# CAN_Injector_rev1.net
KiCad netlist of a schematic drawn in EAGLE
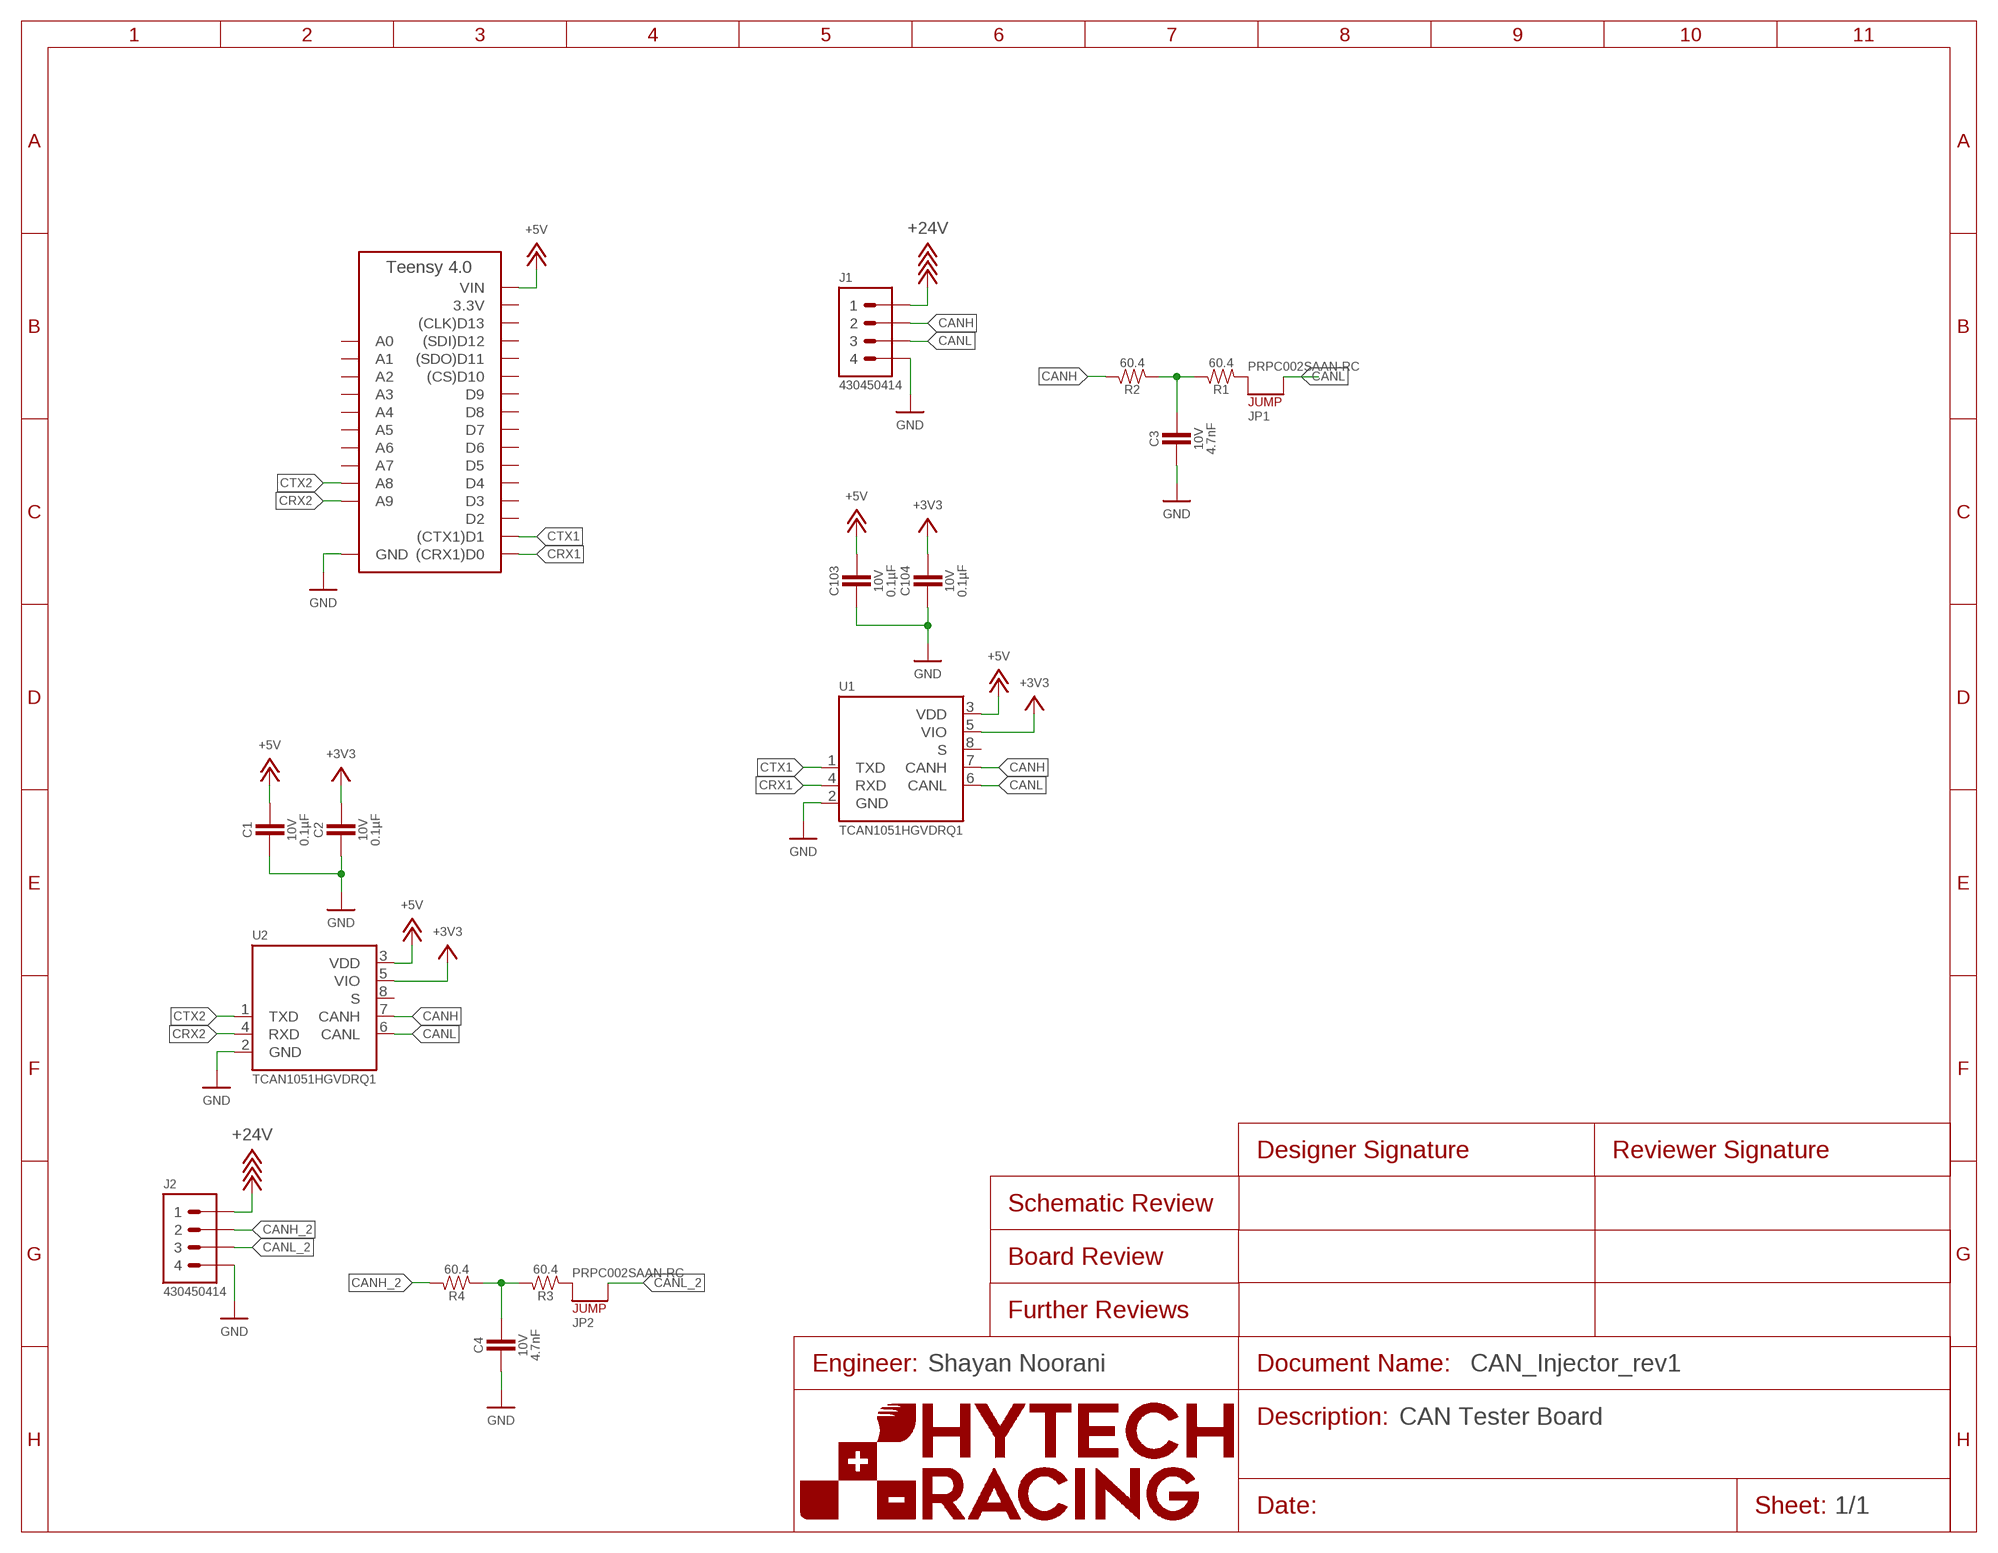
[diagram p0: schematic, sheet 1]

(export (version "E")
  (design (tool "Eeschema 10.0.6"))
  (components
    (comp (ref "A1")
      (value "TEENSY_4.0")
      (footprint "eagle-import:TEENSY_SHORT")
      (libsource (lib "eagle-import") (part "TEENSY_4.0"))
    )
    (comp (ref "C1")
      (value "CAPACITOR_0603_10V_0.1UF")
      (footprint "eagle-import:0603-CAP")
      (fields
        (field (name "CAPACITANCE") "0.1µF")
        (field (name "MANUFACTURER") "Vishay Vitramon")
        (field (name "MPN") "VJ0603Y104JXQPW1BC")
        (field (name "TOLERANCE") "5%")
        (field (name "VOLTAGE") "10V")
      )
      (libsource (lib "eagle-import") (part "CAPACITOR_?_060310V_0.1UF"))
    )
    (comp (ref "C2")
      (value "CAPACITOR_0603_10V_0.1UF")
      (footprint "eagle-import:0603-CAP")
      (fields
        (field (name "CAPACITANCE") "0.1µF")
        (field (name "MANUFACTURER") "Vishay Vitramon")
        (field (name "MPN") "VJ0603Y104JXQPW1BC")
        (field (name "TOLERANCE") "5%")
        (field (name "VOLTAGE") "10V")
      )
      (libsource (lib "eagle-import") (part "CAPACITOR_?_060310V_0.1UF"))
    )
    (comp (ref "C3")
      (value "CAPACITOR_0603_10V_4.7NF")
      (footprint "eagle-import:0603-CAP")
      (fields
        (field (name "CAPACITANCE") "4.7nF")
        (field (name "MANUFACTURER") "Würth Elektronik")
        (field (name "MPN") "885012206012")
        (field (name "TOLERANCE") "10%")
        (field (name "VOLTAGE") "10V")
      )
      (libsource (lib "eagle-import") (part "CAPACITOR_?_060310V_4.7NF"))
    )
    (comp (ref "C4")
      (value "CAPACITOR_0603_10V_4.7NF")
      (footprint "eagle-import:0603-CAP")
      (fields
        (field (name "CAPACITANCE") "4.7nF")
        (field (name "MANUFACTURER") "Würth Elektronik")
        (field (name "MPN") "885012206012")
        (field (name "TOLERANCE") "10%")
        (field (name "VOLTAGE") "10V")
      )
      (libsource (lib "eagle-import") (part "CAPACITOR_?_060310V_4.7NF"))
    )
    (comp (ref "C103")
      (value "CAPACITOR_0603_10V_0.1UF")
      (footprint "eagle-import:0603-CAP")
      (fields
        (field (name "CAPACITANCE") "0.1µF")
        (field (name "MANUFACTURER") "Vishay Vitramon")
        (field (name "MPN") "VJ0603Y104JXQPW1BC")
        (field (name "TOLERANCE") "5%")
        (field (name "VOLTAGE") "10V")
      )
      (libsource (lib "eagle-import") (part "CAPACITOR_?_060310V_0.1UF"))
    )
    (comp (ref "C104")
      (value "CAPACITOR_0603_10V_0.1UF")
      (footprint "eagle-import:0603-CAP")
      (fields
        (field (name "CAPACITANCE") "0.1µF")
        (field (name "MANUFACTURER") "Vishay Vitramon")
        (field (name "MPN") "VJ0603Y104JXQPW1BC")
        (field (name "TOLERANCE") "5%")
        (field (name "VOLTAGE") "10V")
      )
      (libsource (lib "eagle-import") (part "CAPACITOR_?_060310V_0.1UF"))
    )
    (comp (ref "J1")
      (value "CONNECTOR-4_μF_T_V_BLACK")
      (footprint "eagle-import:MOLEX_MICROFIT_PTH_VERTICAL_04_DUAL")
      (fields (field (name "MANUFACTURER") "Molex") (field (name "MPN") "430450414"))
      (libsource (lib "eagle-import") (part "CONNECTOR-4_?_μF_T_VBLACK"))
    )
    (comp (ref "J2")
      (value "CONNECTOR-4_μF_T_V_BLACK")
      (footprint "eagle-import:MOLEX_MICROFIT_PTH_VERTICAL_04_DUAL")
      (fields (field (name "MANUFACTURER") "Molex") (field (name "MPN") "430450414"))
      (libsource (lib "eagle-import") (part "CONNECTOR-4_?_μF_T_VBLACK"))
    )
    (comp (ref "JP1")
      (value "JUMPER__1X02")
      (footprint "eagle-import:1X02")
      (fields
        (field (name "MANUFACTURER") "Sullins Connector Solutions")
        (field (name "MPN") "PRPC002SAAN-RC")
      )
      (libsource (lib "eagle-import") (part "JUMPER_?_1X02"))
    )
    (comp (ref "JP2")
      (value "JUMPER__1X02")
      (footprint "eagle-import:1X02")
      (fields
        (field (name "MANUFACTURER") "Sullins Connector Solutions")
        (field (name "MPN") "PRPC002SAAN-RC")
      )
      (libsource (lib "eagle-import") (part "JUMPER_?_1X02"))
    )
    (comp (ref "R1")
      (value "RESISTOR_0603_60.4")
      (footprint "eagle-import:0603-RES")
      (fields
        (field (name "MANUFACTURER") "Yageo")
        (field (name "MPN") "RC0603FR-0760R4L")
        (field (name "POWER") "0.1W")
        (field (name "RESISTANCE") "60.4")
      )
      (libsource (lib "eagle-import") (part "RESISTOR_?_060360.4"))
    )
    (comp (ref "R2")
      (value "RESISTOR_0603_60.4")
      (footprint "eagle-import:0603-RES")
      (fields
        (field (name "MANUFACTURER") "Yageo")
        (field (name "MPN") "RC0603FR-0760R4L")
        (field (name "POWER") "0.1W")
        (field (name "RESISTANCE") "60.4")
      )
      (libsource (lib "eagle-import") (part "RESISTOR_?_060360.4"))
    )
    (comp (ref "R3")
      (value "RESISTOR_0603_60.4")
      (footprint "eagle-import:0603-RES")
      (fields
        (field (name "MANUFACTURER") "Yageo")
        (field (name "MPN") "RC0603FR-0760R4L")
        (field (name "POWER") "0.1W")
        (field (name "RESISTANCE") "60.4")
      )
      (libsource (lib "eagle-import") (part "RESISTOR_?_060360.4"))
    )
    (comp (ref "R4")
      (value "RESISTOR_0603_60.4")
      (footprint "eagle-import:0603-RES")
      (fields
        (field (name "MANUFACTURER") "Yageo")
        (field (name "MPN") "RC0603FR-0760R4L")
        (field (name "POWER") "0.1W")
        (field (name "RESISTANCE") "60.4")
      )
      (libsource (lib "eagle-import") (part "RESISTOR_?_060360.4"))
    )
    (comp (ref "U1")
      (value "TCAN1051HQV-Q1")
      (footprint "eagle-import:SOIC-08(NARROW,0.15_)")
      (fields (field (name "MANUFACTURER") "Texas Instruments") (field (name "MPN") "TCAN1051HGVDRQ1"))
      (libsource (lib "eagle-import") (part "TCAN1051V-Q1HQ"))
    )
    (comp (ref "U2")
      (value "TCAN1051HQV-Q1")
      (footprint "eagle-import:SOIC-08(NARROW,0.15_)")
      (fields (field (name "MANUFACTURER") "Texas Instruments") (field (name "MPN") "TCAN1051HGVDRQ1"))
      (libsource (lib "eagle-import") (part "TCAN1051V-Q1HQ"))
    )
  )
  (nets
    (net (code "1") (name "+3V3") (class "Default")
      (node (ref "C104") (pin "1") (pinfunction "1_1") (pintype "passive"))
      (node (ref "C2") (pin "1") (pinfunction "1_1") (pintype "passive"))
      (node (ref "U1") (pin "5") (pinfunction "VIO_5") (pintype "power_in"))
      (node (ref "U2") (pin "5") (pinfunction "VIO_5") (pintype "power_in"))
    )
    (net (code "2") (name "+5V") (class "Default")
      (node (ref "A1") (pin "VIN") (pinfunction "VIN_VIN") (pintype "power_in"))
      (node (ref "C1") (pin "1") (pinfunction "1_1") (pintype "passive"))
      (node (ref "C103") (pin "1") (pinfunction "1_1") (pintype "passive"))
      (node (ref "U1") (pin "3") (pinfunction "VDD_3") (pintype "power_in"))
      (node (ref "U2") (pin "3") (pinfunction "VDD_3") (pintype "power_in"))
    )
    (net (code "3") (name "+24V") (class "Default")
      (node (ref "J1") (pin "1") (pinfunction "1_1") (pintype "passive"))
      (node (ref "J2") (pin "1") (pinfunction "1_1") (pintype "passive"))
    )
    (net (code "4") (name "/3.3V") (class "Default")
      (node (ref "A1") (pin "3.3V") (pinfunction "3.3V_3.3V") (pintype "power_in"))
    )
    (net (code "5") (name "CANH") (class "Default")
      (node (ref "J1") (pin "2") (pinfunction "2_2") (pintype "passive"))
      (node (ref "R2") (pin "1") (pinfunction "1_1") (pintype "passive"))
      (node (ref "U1") (pin "7") (pinfunction "CANH_7") (pintype "output"))
      (node (ref "U2") (pin "7") (pinfunction "CANH_7") (pintype "output"))
    )
    (net (code "6") (name "CANH_2") (class "Default")
      (node (ref "J2") (pin "2") (pinfunction "2_2") (pintype "passive"))
      (node (ref "R4") (pin "1") (pinfunction "1_1") (pintype "passive"))
    )
    (net (code "7") (name "CANL") (class "Default")
      (node (ref "J1") (pin "3") (pinfunction "3_3") (pintype "passive"))
      (node (ref "JP1") (pin "2") (pinfunction "2_2") (pintype "passive"))
      (node (ref "U1") (pin "6") (pinfunction "CANL_6") (pintype "bidirectional"))
      (node (ref "U2") (pin "6") (pinfunction "CANL_6") (pintype "bidirectional"))
    )
    (net (code "8") (name "CANL_2") (class "Default")
      (node (ref "J2") (pin "3") (pinfunction "3_3") (pintype "passive"))
      (node (ref "JP2") (pin "2") (pinfunction "2_2") (pintype "passive"))
    )
    (net (code "9") (name "CRX1") (class "Default")
      (node (ref "A1") (pin "D0") (pinfunction "(CRX1)D0_D0") (pintype "bidirectional"))
      (node (ref "U1") (pin "4") (pinfunction "RXD_4") (pintype "output"))
    )
    (net (code "10") (name "CRX2") (class "Default")
      (node (ref "A1") (pin "D23") (pinfunction "A9_D23") (pintype "bidirectional"))
      (node (ref "U2") (pin "4") (pinfunction "RXD_4") (pintype "output"))
    )
    (net (code "11") (name "CTX1") (class "Default")
      (node (ref "A1") (pin "D1") (pinfunction "(CTX1)D1_D1") (pintype "bidirectional"))
      (node (ref "U1") (pin "1") (pinfunction "TXD_1") (pintype "input"))
    )
    (net (code "12") (name "CTX2") (class "Default")
      (node (ref "A1") (pin "D22") (pinfunction "A8_D22") (pintype "bidirectional"))
      (node (ref "U2") (pin "1") (pinfunction "TXD_1") (pintype "input"))
    )
    (net (code "13") (name "GND") (class "Default")
      (node (ref "A1") (pin "AGND/GND") (pinfunction "GND_AGND/GND") (pintype "power_in"))
      (node (ref "A1") (pin "GND") (pinfunction "GND_GND") (pintype "power_in"))
      (node (ref "C1") (pin "2") (pinfunction "2_2") (pintype "passive"))
      (node (ref "C103") (pin "2") (pinfunction "2_2") (pintype "passive"))
      (node (ref "C104") (pin "2") (pinfunction "2_2") (pintype "passive"))
      (node (ref "C2") (pin "2") (pinfunction "2_2") (pintype "passive"))
      (node (ref "C3") (pin "2") (pinfunction "2_2") (pintype "passive"))
      (node (ref "C4") (pin "2") (pinfunction "2_2") (pintype "passive"))
      (node (ref "J1") (pin "4") (pinfunction "4_4") (pintype "passive"))
      (node (ref "J2") (pin "4") (pinfunction "4_4") (pintype "passive"))
      (node (ref "U1") (pin "2") (pinfunction "GND_2") (pintype "power_in"))
      (node (ref "U2") (pin "2") (pinfunction "GND_2") (pintype "power_in"))
    )
    (net (code "14") (name "Net-(C3-Pad1)") (class "Default")
      (node (ref "C3") (pin "1") (pinfunction "1_1") (pintype "passive"))
      (node (ref "R1") (pin "1") (pinfunction "1_1") (pintype "passive"))
      (node (ref "R2") (pin "2") (pinfunction "2_2") (pintype "passive"))
    )
    (net (code "15") (name "Net-(C4-Pad1)") (class "Default")
      (node (ref "C4") (pin "1") (pinfunction "1_1") (pintype "passive"))
      (node (ref "R3") (pin "1") (pinfunction "1_1") (pintype "passive"))
      (node (ref "R4") (pin "2") (pinfunction "2_2") (pintype "passive"))
    )
    (net (code "16") (name "Net-(JP1-Pad1)") (class "Default")
      (node (ref "JP1") (pin "1") (pinfunction "1_1") (pintype "passive"))
      (node (ref "R1") (pin "2") (pinfunction "2_2") (pintype "passive"))
    )
    (net (code "17") (name "Net-(JP2-Pad1)") (class "Default")
      (node (ref "JP2") (pin "1") (pinfunction "1_1") (pintype "passive"))
      (node (ref "R3") (pin "2") (pinfunction "2_2") (pintype "passive"))
    )
    (net (code "18") (name "unconnected-(A1-(CLK)D13-PadD13)") (class "Default")
      (node (ref "A1") (pin "D13") (pinfunction "(CLK)D13_D13") (pintype "bidirectional"))
    )
    (net (code "19") (name "unconnected-(A1-(CS)D10-PadD10)") (class "Default")
      (node (ref "A1") (pin "D10") (pinfunction "(CS)D10_D10") (pintype "bidirectional"))
    )
    (net (code "20") (name "unconnected-(A1-(SDI)D12-PadD12)") (class "Default")
      (node (ref "A1") (pin "D12") (pinfunction "(SDI)D12_D12") (pintype "bidirectional"))
    )
    (net (code "21") (name "unconnected-(A1-(SDO)D11-PadD11)") (class "Default")
      (node (ref "A1") (pin "D11") (pinfunction "(SDO)D11_D11") (pintype "bidirectional"))
    )
    (net (code "22") (name "unconnected-(A1-A0-PadD14)") (class "Default")
      (node (ref "A1") (pin "D14") (pinfunction "A0_D14") (pintype "bidirectional"))
    )
    (net (code "23") (name "unconnected-(A1-A1-PadD15)") (class "Default")
      (node (ref "A1") (pin "D15") (pinfunction "A1_D15") (pintype "bidirectional"))
    )
    (net (code "24") (name "unconnected-(A1-A2-PadD16)") (class "Default")
      (node (ref "A1") (pin "D16") (pinfunction "A2_D16") (pintype "bidirectional"))
    )
    (net (code "25") (name "unconnected-(A1-A3-PadD17)") (class "Default")
      (node (ref "A1") (pin "D17") (pinfunction "A3_D17") (pintype "bidirectional"))
    )
    (net (code "26") (name "unconnected-(A1-A4-PadD18)") (class "Default")
      (node (ref "A1") (pin "D18") (pinfunction "A4_D18") (pintype "bidirectional"))
    )
    (net (code "27") (name "unconnected-(A1-A5-PadD19)") (class "Default")
      (node (ref "A1") (pin "D19") (pinfunction "A5_D19") (pintype "bidirectional"))
    )
    (net (code "28") (name "unconnected-(A1-A6-PadD20)") (class "Default")
      (node (ref "A1") (pin "D20") (pinfunction "A6_D20") (pintype "bidirectional"))
    )
    (net (code "29") (name "unconnected-(A1-A7-PadD21)") (class "Default")
      (node (ref "A1") (pin "D21") (pinfunction "A7_D21") (pintype "bidirectional"))
    )
    (net (code "30") (name "unconnected-(A1-PadD2)") (class "Default")
      (node (ref "A1") (pin "D2") (pinfunction "D2_D2") (pintype "bidirectional"))
    )
    (net (code "31") (name "unconnected-(A1-PadD3)") (class "Default")
      (node (ref "A1") (pin "D3") (pinfunction "D3_D3") (pintype "bidirectional"))
    )
    (net (code "32") (name "unconnected-(A1-PadD4)") (class "Default")
      (node (ref "A1") (pin "D4") (pinfunction "D4_D4") (pintype "bidirectional"))
    )
    (net (code "33") (name "unconnected-(A1-PadD5)") (class "Default")
      (node (ref "A1") (pin "D5") (pinfunction "D5_D5") (pintype "bidirectional"))
    )
    (net (code "34") (name "unconnected-(A1-PadD6)") (class "Default")
      (node (ref "A1") (pin "D6") (pinfunction "D6_D6") (pintype "bidirectional"))
    )
    (net (code "35") (name "unconnected-(A1-PadD7)") (class "Default")
      (node (ref "A1") (pin "D7") (pinfunction "D7_D7") (pintype "bidirectional"))
    )
    (net (code "36") (name "unconnected-(A1-PadD8)") (class "Default")
      (node (ref "A1") (pin "D8") (pinfunction "D8_D8") (pintype "bidirectional"))
    )
    (net (code "37") (name "unconnected-(A1-PadD9)") (class "Default")
      (node (ref "A1") (pin "D9") (pinfunction "D9_D9") (pintype "bidirectional"))
    )
    (net (code "38") (name "unconnected-(U1-S-Pad8)") (class "Default")
      (node (ref "U1") (pin "8") (pinfunction "S_8") (pintype "input"))
    )
    (net (code "39") (name "unconnected-(U2-S-Pad8)") (class "Default")
      (node (ref "U2") (pin "8") (pinfunction "S_8") (pintype "input"))
    )
  )
)
